# Input_interface_for_DBL165_ShiftIn_Reg.net
KiCad netlist of a schematic drawn in Altium Designer
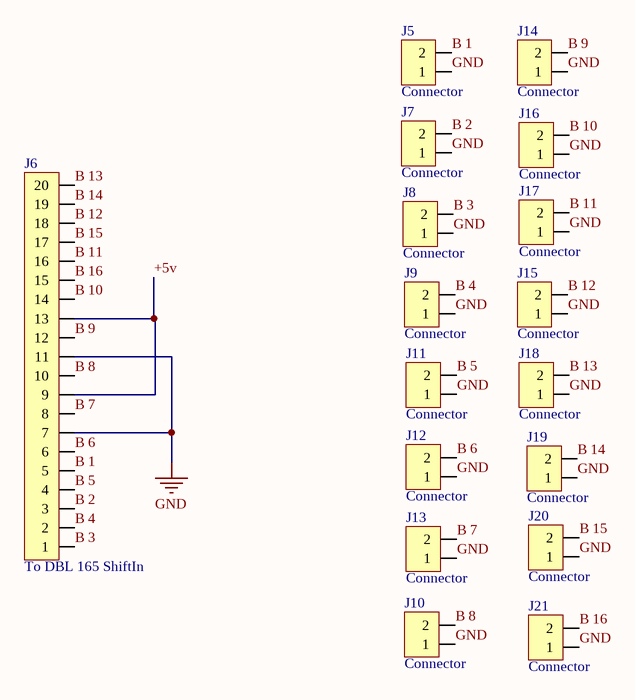
[diagram p0: Input interface for DBL165 ShiftIn Reg.SchDoc]

(export (version "E")
  (design (tool "Eeschema 10.0.6"))
  (components
    (comp (ref "J5")
      (value "Connector")
      (footprint "Connector:DG301 5mm 2p")
      (description "DG301 series")
      (libsource (lib "Connector") (part "DG301-5.0-2P12"))
    )
    (comp (ref "J6")
      (value "To DBL 165 ShiftIn")
      (footprint "Connector:LINE 2.54 x 20D (2 x 10) - BH")
      (description "Vert, Dbl line, Male")
      (libsource (lib "Connector") (part "PLD-20 (2 x 10)"))
    )
    (comp (ref "J7")
      (value "Connector")
      (footprint "Connector:DG301 5mm 2p")
      (description "DG301 series")
      (libsource (lib "Connector") (part "DG301-5.0-2P12"))
    )
    (comp (ref "J8")
      (value "Connector")
      (footprint "Connector:DG301 5mm 2p")
      (description "DG301 series")
      (libsource (lib "Connector") (part "DG301-5.0-2P12"))
    )
    (comp (ref "J9")
      (value "Connector")
      (footprint "Connector:DG301 5mm 2p")
      (description "DG301 series")
      (libsource (lib "Connector") (part "DG301-5.0-2P12"))
    )
    (comp (ref "J10")
      (value "Connector")
      (footprint "Connector:DG301 5mm 2p")
      (description "DG301 series")
      (libsource (lib "Connector") (part "DG301-5.0-2P12"))
    )
    (comp (ref "J11")
      (value "Connector")
      (footprint "Connector:DG301 5mm 2p")
      (description "DG301 series")
      (libsource (lib "Connector") (part "DG301-5.0-2P12"))
    )
    (comp (ref "J12")
      (value "Connector")
      (footprint "Connector:DG301 5mm 2p")
      (description "DG301 series")
      (libsource (lib "Connector") (part "DG301-5.0-2P12"))
    )
    (comp (ref "J13")
      (value "Connector")
      (footprint "Connector:DG301 5mm 2p")
      (description "DG301 series")
      (libsource (lib "Connector") (part "DG301-5.0-2P12"))
    )
    (comp (ref "J14")
      (value "Connector")
      (footprint "Connector:DG301 5mm 2p")
      (description "DG301 series")
      (libsource (lib "Connector") (part "DG301-5.0-2P12"))
    )
    (comp (ref "J15")
      (value "Connector")
      (footprint "Connector:DG301 5mm 2p")
      (description "DG301 series")
      (libsource (lib "Connector") (part "DG301-5.0-2P12"))
    )
    (comp (ref "J16")
      (value "Connector")
      (footprint "Connector:DG301 5mm 2p")
      (description "DG301 series")
      (libsource (lib "Connector") (part "DG301-5.0-2P12"))
    )
    (comp (ref "J17")
      (value "Connector")
      (footprint "Connector:DG301 5mm 2p")
      (description "DG301 series")
      (libsource (lib "Connector") (part "DG301-5.0-2P12"))
    )
    (comp (ref "J18")
      (value "Connector")
      (footprint "Connector:DG301 5mm 2p")
      (description "DG301 series")
      (libsource (lib "Connector") (part "DG301-5.0-2P12"))
    )
    (comp (ref "J19")
      (value "Connector")
      (footprint "Connector:DG301 5mm 2p")
      (description "DG301 series")
      (libsource (lib "Connector") (part "DG301-5.0-2P12"))
    )
    (comp (ref "J20")
      (value "Connector")
      (footprint "Connector:DG301 5mm 2p")
      (description "DG301 series")
      (libsource (lib "Connector") (part "DG301-5.0-2P12"))
    )
    (comp (ref "J21")
      (value "Connector")
      (footprint "Connector:DG301 5mm 2p")
      (description "DG301 series")
      (libsource (lib "Connector") (part "DG301-5.0-2P12"))
    )
  )
  (nets
    (net (code "1") (name "/+5v") (class "Default")
      (node (ref "J6") (pin "13") (pinfunction "13_13") (pintype "passive"))
      (node (ref "J6") (pin "9") (pinfunction "9_9") (pintype "passive"))
    )
    (net (code "2") (name "/B 1") (class "Default")
      (node (ref "J5") (pin "2") (pinfunction "2_2") (pintype "passive"))
      (node (ref "J6") (pin "5") (pinfunction "5_5") (pintype "passive"))
    )
    (net (code "3") (name "/B 2") (class "Default")
      (node (ref "J6") (pin "3") (pinfunction "3_3") (pintype "passive"))
      (node (ref "J7") (pin "2") (pinfunction "2_2") (pintype "passive"))
    )
    (net (code "4") (name "/B 3") (class "Default")
      (node (ref "J6") (pin "1") (pinfunction "1_1") (pintype "passive"))
      (node (ref "J8") (pin "2") (pinfunction "2_2") (pintype "passive"))
    )
    (net (code "5") (name "/B 4") (class "Default")
      (node (ref "J6") (pin "2") (pinfunction "2_2") (pintype "passive"))
      (node (ref "J9") (pin "2") (pinfunction "2_2") (pintype "passive"))
    )
    (net (code "6") (name "/B 5") (class "Default")
      (node (ref "J11") (pin "2") (pinfunction "2_2") (pintype "passive"))
      (node (ref "J6") (pin "4") (pinfunction "4_4") (pintype "passive"))
    )
    (net (code "7") (name "/B 6") (class "Default")
      (node (ref "J12") (pin "2") (pinfunction "2_2") (pintype "passive"))
      (node (ref "J6") (pin "6") (pinfunction "6_6") (pintype "passive"))
    )
    (net (code "8") (name "/B 7") (class "Default")
      (node (ref "J13") (pin "2") (pinfunction "2_2") (pintype "passive"))
      (node (ref "J6") (pin "8") (pinfunction "8_8") (pintype "passive"))
    )
    (net (code "9") (name "/B 8") (class "Default")
      (node (ref "J10") (pin "2") (pinfunction "2_2") (pintype "passive"))
      (node (ref "J6") (pin "10") (pinfunction "10_10") (pintype "passive"))
    )
    (net (code "10") (name "/B 9") (class "Default")
      (node (ref "J14") (pin "2") (pinfunction "2_2") (pintype "passive"))
      (node (ref "J6") (pin "12") (pinfunction "12_12") (pintype "passive"))
    )
    (net (code "11") (name "/B 10") (class "Default")
      (node (ref "J16") (pin "2") (pinfunction "2_2") (pintype "passive"))
      (node (ref "J6") (pin "14") (pinfunction "14_14") (pintype "passive"))
    )
    (net (code "12") (name "/B 11") (class "Default")
      (node (ref "J17") (pin "2") (pinfunction "2_2") (pintype "passive"))
      (node (ref "J6") (pin "16") (pinfunction "16_16") (pintype "passive"))
    )
    (net (code "13") (name "/B 12") (class "Default")
      (node (ref "J15") (pin "2") (pinfunction "2_2") (pintype "passive"))
      (node (ref "J6") (pin "18") (pinfunction "18_18") (pintype "passive"))
    )
    (net (code "14") (name "/B 13") (class "Default")
      (node (ref "J18") (pin "2") (pinfunction "2_2") (pintype "passive"))
      (node (ref "J6") (pin "20") (pinfunction "20_20") (pintype "passive"))
    )
    (net (code "15") (name "/B 14") (class "Default")
      (node (ref "J19") (pin "2") (pinfunction "2_2") (pintype "passive"))
      (node (ref "J6") (pin "19") (pinfunction "19_19") (pintype "passive"))
    )
    (net (code "16") (name "/B 15") (class "Default")
      (node (ref "J20") (pin "2") (pinfunction "2_2") (pintype "passive"))
      (node (ref "J6") (pin "17") (pinfunction "17_17") (pintype "passive"))
    )
    (net (code "17") (name "/B 16") (class "Default")
      (node (ref "J21") (pin "2") (pinfunction "2_2") (pintype "passive"))
      (node (ref "J6") (pin "15") (pinfunction "15_15") (pintype "passive"))
    )
    (net (code "18") (name "GND") (class "Default")
      (node (ref "J10") (pin "1") (pinfunction "1_1") (pintype "passive"))
      (node (ref "J11") (pin "1") (pinfunction "1_1") (pintype "passive"))
      (node (ref "J12") (pin "1") (pinfunction "1_1") (pintype "passive"))
      (node (ref "J13") (pin "1") (pinfunction "1_1") (pintype "passive"))
      (node (ref "J14") (pin "1") (pinfunction "1_1") (pintype "passive"))
      (node (ref "J15") (pin "1") (pinfunction "1_1") (pintype "passive"))
      (node (ref "J16") (pin "1") (pinfunction "1_1") (pintype "passive"))
      (node (ref "J17") (pin "1") (pinfunction "1_1") (pintype "passive"))
      (node (ref "J18") (pin "1") (pinfunction "1_1") (pintype "passive"))
      (node (ref "J19") (pin "1") (pinfunction "1_1") (pintype "passive"))
      (node (ref "J20") (pin "1") (pinfunction "1_1") (pintype "passive"))
      (node (ref "J21") (pin "1") (pinfunction "1_1") (pintype "passive"))
      (node (ref "J5") (pin "1") (pinfunction "1_1") (pintype "passive"))
      (node (ref "J6") (pin "11") (pinfunction "11_11") (pintype "passive"))
      (node (ref "J6") (pin "7") (pinfunction "7_7") (pintype "passive"))
      (node (ref "J7") (pin "1") (pinfunction "1_1") (pintype "passive"))
      (node (ref "J8") (pin "1") (pinfunction "1_1") (pintype "passive"))
      (node (ref "J9") (pin "1") (pinfunction "1_1") (pintype "passive"))
    )
  )
)
